# accel_mag.net
KiCad netlist of a schematic drawn in Altium Designer
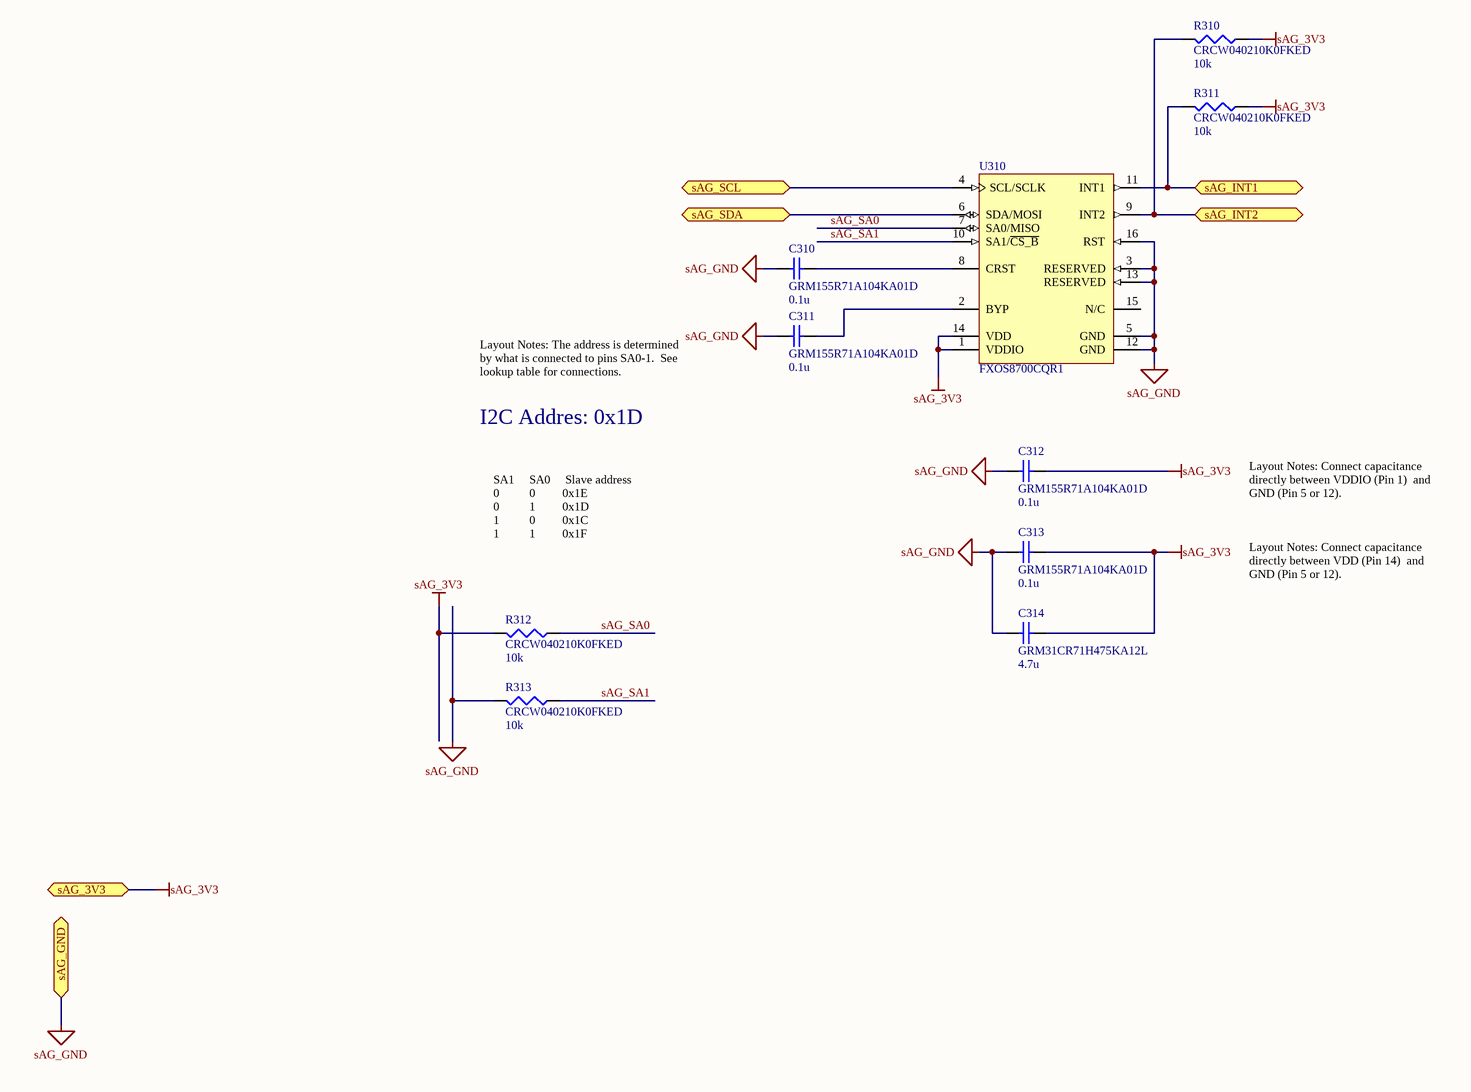
[diagram p0: _accel_mag.SchDoc]

(export (version "E")
  (design (tool "Eeschema 10.0.6"))
  (components
    (comp (ref "C310")
      (value "GRM155R71A104KA01D")
      (footprint "0402")
      (description "-55-125C, 1005, 10V, X7R, ±10%")
      (fields (field (name "ALTIUM_VALUE") "0.1u"))
      (libsource (lib "standard_capacitors") (part "GRM155R71AxxxKdddd"))
    )
    (comp (ref "C311")
      (value "GRM155R71A104KA01D")
      (footprint "0402")
      (description "-55-125C, 1005, 10V, X7R, ±10%")
      (fields (field (name "ALTIUM_VALUE") "0.1u"))
      (libsource (lib "standard_capacitors") (part "GRM155R71AxxxKdddd"))
    )
    (comp (ref "C312")
      (value "GRM155R71A104KA01D")
      (footprint "0402")
      (description "-55-125C, 1005, 10V, X7R, ±10%")
      (fields (field (name "ALTIUM_VALUE") "0.1u"))
      (libsource (lib "standard_capacitors") (part "GRM155R71AxxxKdddd"))
    )
    (comp (ref "C313")
      (value "GRM155R71A104KA01D")
      (footprint "0402")
      (description "-55-125C, 1005, 10V, X7R, ±10%")
      (fields (field (name "ALTIUM_VALUE") "0.1u"))
      (libsource (lib "standard_capacitors") (part "GRM155R71AxxxKdddd"))
    )
    (comp (ref "C314")
      (value "GRM31CR71H475KA12L")
      (footprint "1206")
      (description "-55-125C, 3216, 50V, X7R, ±10%")
      (fields (field (name "ALTIUM_VALUE") "4.7u"))
      (libsource (lib "standard_capacitors") (part "GRM31CR71HxxxKdddd"))
    )
    (comp (ref "R310")
      (value "CRCW040210K0FKED")
      (footprint "0402")
      (description "0.125W, -55-155C, 1005, 50V, ±1%")
      (fields (field (name "ALTIUM_VALUE") "10k"))
      (libsource (lib "standard_resistors") (part "CRCW0402xxxxFKED"))
    )
    (comp (ref "R311")
      (value "CRCW040210K0FKED")
      (footprint "0402")
      (description "0.125W, -55-155C, 1005, 50V, ±1%")
      (fields (field (name "ALTIUM_VALUE") "10k"))
      (libsource (lib "standard_resistors") (part "CRCW0402xxxxFKED"))
    )
    (comp (ref "R312")
      (value "CRCW040210K0FKED")
      (footprint "0402")
      (description "0.125W, -55-155C, 1005, 50V, ±1%")
      (fields (field (name "ALTIUM_VALUE") "10k"))
      (libsource (lib "standard_resistors") (part "CRCW0402xxxxFKED"))
    )
    (comp (ref "R313")
      (value "CRCW040210K0FKED")
      (footprint "0402")
      (description "0.125W, -55-155C, 1005, 50V, ±1%")
      (fields (field (name "ALTIUM_VALUE") "10k"))
      (libsource (lib "standard_resistors") (part "CRCW0402xxxxFKED"))
    )
    (comp (ref "U310")
      (value "FXOS8700CQR1")
      (footprint "FREE-QFN-16-3000X3000DE_V")
      (fields (field (name "MANUFACTURER") "Freescale"))
      (libsource (lib "Altium Content Vault") (part "FREE-FXOS8700CQR1-16"))
    )
  )
  (nets
    (net (code "1") (name "/sAG_INT1") (class "Default")
      (node (ref "R311") (pin "2") (pinfunction "2_2") (pintype "passive"))
      (node (ref "U310") (pin "11") (pinfunction "INT1_11") (pintype "output"))
    )
    (net (code "2") (name "/sAG_INT2") (class "Default")
      (node (ref "R310") (pin "2") (pinfunction "2_2") (pintype "passive"))
      (node (ref "U310") (pin "9") (pinfunction "INT2_9") (pintype "output"))
    )
    (net (code "3") (name "/sAG_SA0") (class "Default")
      (node (ref "R312") (pin "1") (pinfunction "1_1") (pintype "passive"))
      (node (ref "U310") (pin "7") (pinfunction "SA0/MISO_7") (pintype "bidirectional"))
    )
    (net (code "4") (name "/sAG_SA1") (class "Default")
      (node (ref "R313") (pin "1") (pinfunction "1_1") (pintype "passive"))
      (node (ref "U310") (pin "10") (pinfunction "SA1/~{CS_B}_10") (pintype "input"))
    )
    (net (code "5") (name "/sAG_SCL") (class "Default")
      (node (ref "U310") (pin "4") (pinfunction "SCL/SCLK_4") (pintype "input"))
    )
    (net (code "6") (name "/sAG_SDA") (class "Default")
      (node (ref "U310") (pin "6") (pinfunction "SDA/MOSI_6") (pintype "bidirectional"))
    )
    (net (code "7") (name "Net-(U310-BYP)") (class "Default")
      (node (ref "C311") (pin "1") (pinfunction "1_1") (pintype "passive"))
      (node (ref "U310") (pin "2") (pinfunction "BYP_2") (pintype "passive"))
    )
    (net (code "8") (name "Net-(U310-CRST)") (class "Default")
      (node (ref "C310") (pin "1") (pinfunction "1_1") (pintype "passive"))
      (node (ref "U310") (pin "8") (pinfunction "CRST_8") (pintype "passive"))
    )
    (net (code "9") (name "sAG_3V3") (class "Default")
      (node (ref "C312") (pin "2") (pinfunction "2_2") (pintype "passive"))
      (node (ref "C313") (pin "2") (pinfunction "2_2") (pintype "passive"))
      (node (ref "C314") (pin "2") (pinfunction "2_2") (pintype "passive"))
      (node (ref "R310") (pin "1") (pinfunction "1_1") (pintype "passive"))
      (node (ref "R311") (pin "1") (pinfunction "1_1") (pintype "passive"))
      (node (ref "R312") (pin "2") (pinfunction "2_2") (pintype "passive"))
      (node (ref "U310") (pin "1") (pinfunction "VDDIO_1") (pintype "power_in"))
      (node (ref "U310") (pin "14") (pinfunction "VDD_14") (pintype "power_in"))
    )
    (net (code "10") (name "sAG_GND") (class "Default")
      (node (ref "C310") (pin "2") (pinfunction "2_2") (pintype "passive"))
      (node (ref "C311") (pin "2") (pinfunction "2_2") (pintype "passive"))
      (node (ref "C312") (pin "1") (pinfunction "1_1") (pintype "passive"))
      (node (ref "C313") (pin "1") (pinfunction "1_1") (pintype "passive"))
      (node (ref "C314") (pin "1") (pinfunction "1_1") (pintype "passive"))
      (node (ref "R313") (pin "2") (pinfunction "2_2") (pintype "passive"))
      (node (ref "U310") (pin "12") (pinfunction "GND_12") (pintype "power_in"))
      (node (ref "U310") (pin "13") (pinfunction "RESERVED_13") (pintype "input"))
      (node (ref "U310") (pin "16") (pinfunction "RST_16") (pintype "input"))
      (node (ref "U310") (pin "3") (pinfunction "RESERVED_3") (pintype "input"))
      (node (ref "U310") (pin "5") (pinfunction "GND_5") (pintype "power_in"))
    )
    (net (code "11") (name "unconnected-(U310-N{slash}C-Pad15)") (class "Default")
      (node (ref "U310") (pin "15") (pinfunction "N/C_15") (pintype "passive"))
    )
  )
)
